# tempsens_tsys01.net
KiCad netlist of a schematic drawn in EAGLE
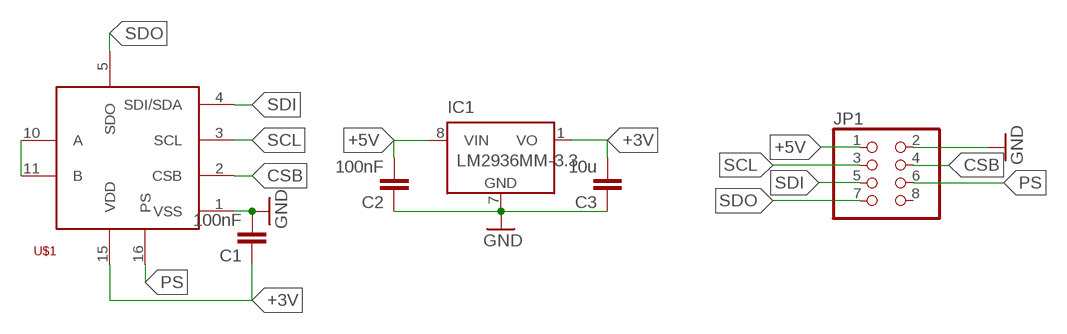
[diagram p0: schematic, sheet 1]

(export (version "E")
  (design (tool "Eeschema 10.0.6"))
  (components
    (comp (ref "C1")
      (value "100nF")
      (footprint "eagle-import:C0603K")
      (libsource (lib "eagle-import") (part "resistor_C-EUC0603K"))
    )
    (comp (ref "C2")
      (value "100nF")
      (footprint "eagle-import:C0603K")
      (libsource (lib "eagle-import") (part "resistor_C-EUC0603K"))
    )
    (comp (ref "C3")
      (value "10u")
      (footprint "eagle-import:C0805")
      (libsource (lib "eagle-import") (part "C-EUC0805"))
    )
    (comp (ref "IC1")
      (value "LM2936MM-3.3")
      (footprint "eagle-import:MINI-SO8")
      (fields (field (name "MF") "NATIONAL SEMICONDUCTOR") (field (name "MPN") "LM2936MM-3.3/NOPB"))
      (libsource (lib "eagle-import") (part "LM2936?MM-3.3"))
    )
    (comp (ref "JP1")
      (value "PINHD-2X4_2.00")
      (footprint "eagle-import:2X04M")
      (libsource (lib "eagle-import") (part "PINHD-2X4_2.00"))
    )
    (comp (ref "U$1")
      (value "TSYS01NOPAD")
      (footprint "eagle-import:TSYS01_NOPAD")
      (libsource (lib "eagle-import") (part "TSYS01NOPAD"))
    )
  )
  (nets
    (net (code "1") (name "+3V") (class "Default")
      (node (ref "C1") (pin "1") (pinfunction "1_1") (pintype "passive"))
      (node (ref "C3") (pin "2") (pinfunction "2_2") (pintype "passive"))
      (node (ref "IC1") (pin "1") (pinfunction "VO_1") (pintype "passive"))
      (node (ref "U$1") (pin "15") (pinfunction "VDD_15") (pintype "bidirectional"))
    )
    (net (code "2") (name "+5V") (class "Default")
      (node (ref "C2") (pin "2") (pinfunction "2_2") (pintype "passive"))
      (node (ref "IC1") (pin "8") (pinfunction "VIN_8") (pintype "input"))
      (node (ref "JP1") (pin "1") (pinfunction "1_1") (pintype "passive"))
    )
    (net (code "3") (name "CSB") (class "Default")
      (node (ref "JP1") (pin "4") (pinfunction "4_4") (pintype "passive"))
      (node (ref "U$1") (pin "2") (pinfunction "CSB_2") (pintype "bidirectional"))
    )
    (net (code "4") (name "GND") (class "Default")
      (node (ref "C1") (pin "2") (pinfunction "2_2") (pintype "passive"))
      (node (ref "C2") (pin "1") (pinfunction "1_1") (pintype "passive"))
      (node (ref "C3") (pin "1") (pinfunction "1_1") (pintype "passive"))
      (node (ref "IC1") (pin "7") (pinfunction "GND_7") (pintype "passive"))
      (node (ref "JP1") (pin "2") (pinfunction "2_2") (pintype "passive"))
      (node (ref "U$1") (pin "1") (pinfunction "VSS_1") (pintype "bidirectional"))
    )
    (net (code "5") (name "Net-(U$1-A)") (class "Default")
      (node (ref "U$1") (pin "10") (pinfunction "A_10") (pintype "bidirectional"))
      (node (ref "U$1") (pin "11") (pinfunction "B_11") (pintype "bidirectional"))
    )
    (net (code "6") (name "PS") (class "Default")
      (node (ref "JP1") (pin "6") (pinfunction "6_6") (pintype "passive"))
      (node (ref "U$1") (pin "16") (pinfunction "PS_16") (pintype "bidirectional"))
    )
    (net (code "7") (name "SCL") (class "Default")
      (node (ref "JP1") (pin "3") (pinfunction "3_3") (pintype "passive"))
      (node (ref "U$1") (pin "3") (pinfunction "SCL_3") (pintype "bidirectional"))
    )
    (net (code "8") (name "SDI") (class "Default")
      (node (ref "JP1") (pin "5") (pinfunction "5_5") (pintype "passive"))
      (node (ref "U$1") (pin "4") (pinfunction "SDI/SDA_4") (pintype "bidirectional"))
    )
    (net (code "9") (name "SDO") (class "Default")
      (node (ref "JP1") (pin "7") (pinfunction "7_7") (pintype "passive"))
      (node (ref "U$1") (pin "5") (pinfunction "SDO_5") (pintype "bidirectional"))
    )
    (net (code "10") (name "unconnected-(JP1-Pad8)") (class "Default")
      (node (ref "JP1") (pin "8") (pinfunction "8_8") (pintype "passive"))
    )
  )
)
